# TDII_PWR_R00.net
KiCad netlist of a schematic drawn in Altium Designer
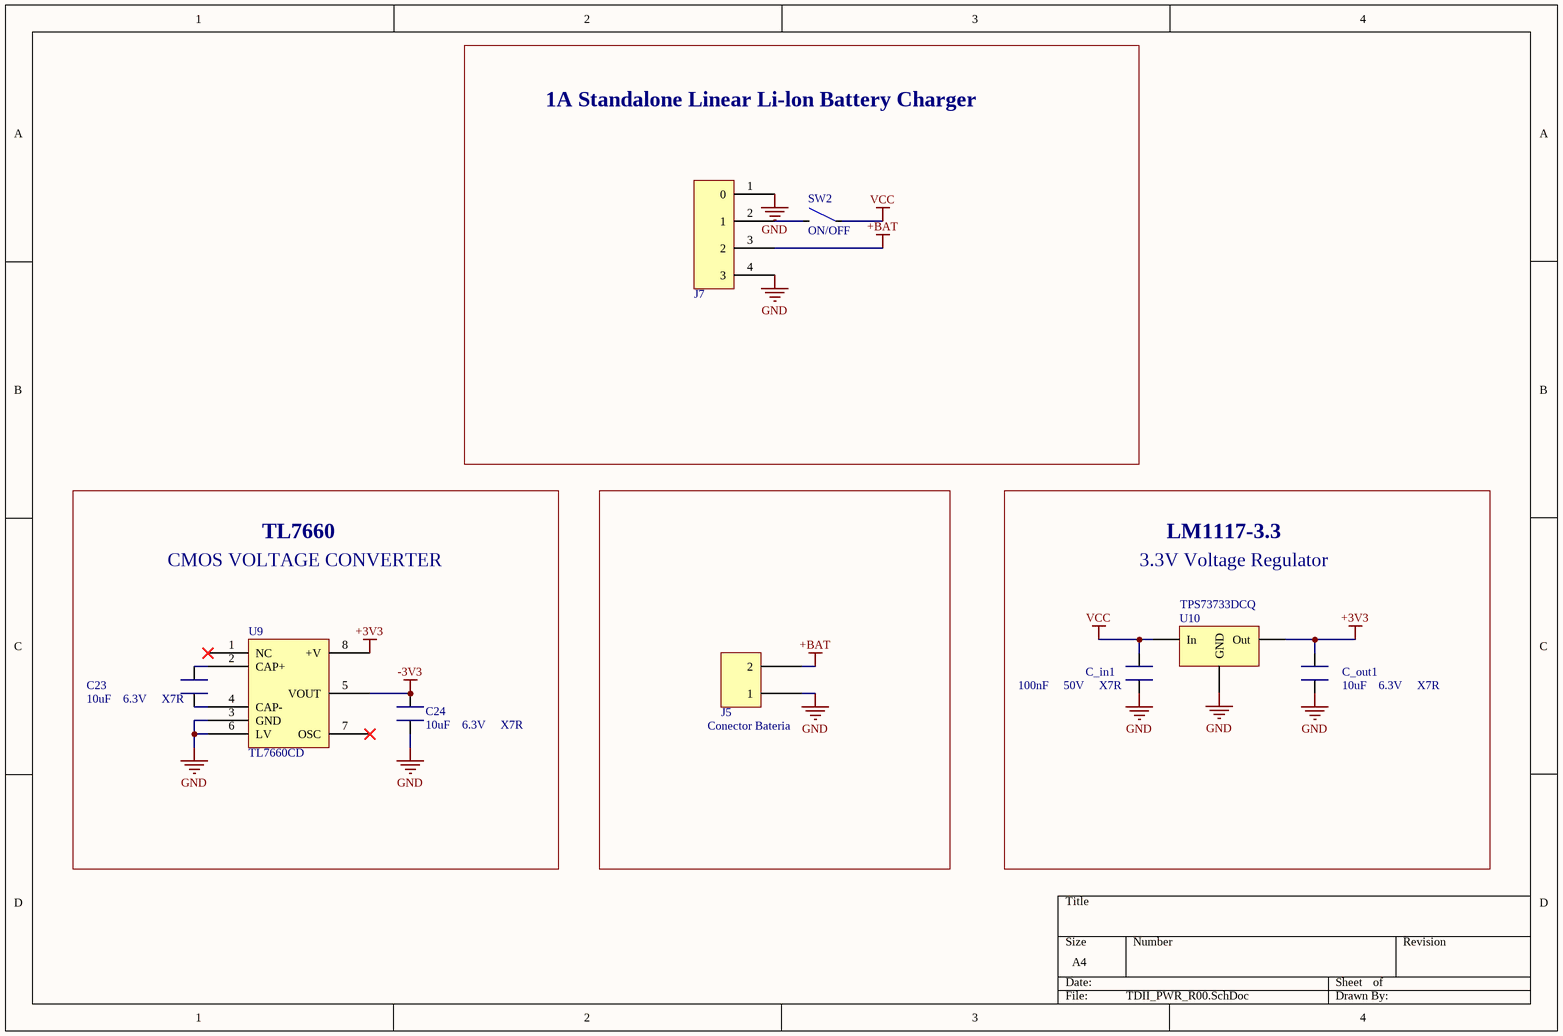
[diagram p0: TDII_PWR_R00.SchDoc]

(export (version "E")
  (design (tool "Eeschema 10.0.6"))
  (components
    (comp (ref "C23")
      (value "10uF    6.3V     X7R")
      (footprint "C_0805")
      (libsource (lib "TDII_SCH_LIB_R00") (part "CAP"))
    )
    (comp (ref "C24") (value "10uF    6.3V     X7R") (footprint "C_0805") (libsource (lib "") (part "CAP_1")))
    (comp (ref "C_in1")
      (value "100nF     50V     X7R")
      (footprint "C_0805")
      (libsource (lib "TDII_SCH_LIB_R00") (part "CAP"))
    )
    (comp (ref "C_out1")
      (value "10uF    6.3V     X7R")
      (footprint "C_0805")
      (libsource (lib "TDII_SCH_LIB_R00") (part "CAP"))
    )
    (comp (ref "J5")
      (value "Conector Bateria")
      (footprint "HEADER_1x2")
      (libsource (lib "TDII_SCH_LIB_R00") (part "Conector_2 ( 0.100{dblquote})"))
    )
    (comp (ref "J7")
      (value "Conector 0.100\" - 4 pines")
      (footprint "HEADER_CHARGER")
      (libsource (lib "Conectores") (part "Conector 0.100{dblquote} - 4 pines"))
    )
    (comp (ref "SW2")
      (value "ON/OFF")
      (footprint "HEADER_1x2")
      (description "Switch, generic")
      (libsource (lib "IFS_Altium") (part "SWITCH"))
    )
    (comp (ref "U9")
      (value "TL7660CD")
      (footprint "SOI8")
      (libsource (lib "TDII_SCH_LIB_R00") (part "TL7660"))
    )
    (comp (ref "U10")
      (value "TPS73733DCQ")
      (footprint "SOT-223-4")
      (description "LDO Voltage Regulators Sgl Output LDO 800mA Fixed Int Crnt limit")
      (fields (field (name "MANUFACTURER") "Texas Instruments"))
      (libsource (lib "IFS_Altium") (part "TLV1117-33CKVURG3"))
    )
  )
  (nets
    (net (code "1") (name "+3V3") (class "Default")
      (node (ref "C_out1") (pin "1") (pinfunction "1_1") (pintype "passive"))
      (node (ref "U10") (pin "2") (pinfunction "Out_2") (pintype "passive"))
      (node (ref "U9") (pin "8") (pinfunction "+V_8") (pintype "passive"))
    )
    (net (code "2") (name "+BAT") (class "Default")
      (node (ref "J5") (pin "1") (pinfunction "2_1") (pintype "passive"))
      (node (ref "J7") (pin "3") (pinfunction "2_3") (pintype "passive"))
    )
    (net (code "3") (name "-3V3") (class "Default")
      (node (ref "C24") (pin "1") (pinfunction "1_1") (pintype "passive"))
      (node (ref "U9") (pin "5") (pinfunction "VOUT_5") (pintype "passive"))
    )
    (net (code "4") (name "GND") (class "Default")
      (node (ref "C24") (pin "2") (pinfunction "2_2") (pintype "passive"))
      (node (ref "C_in1") (pin "2") (pinfunction "2_2") (pintype "passive"))
      (node (ref "C_out1") (pin "2") (pinfunction "2_2") (pintype "passive"))
      (node (ref "J5") (pin "2") (pinfunction "1_2") (pintype "passive"))
      (node (ref "J7") (pin "1") (pinfunction "0_1") (pintype "passive"))
      (node (ref "J7") (pin "4") (pinfunction "3_4") (pintype "passive"))
      (node (ref "U10") (pin "1") (pinfunction "GND_1") (pintype "passive"))
      (node (ref "U9") (pin "3") (pinfunction "GND_3") (pintype "passive"))
      (node (ref "U9") (pin "6") (pinfunction "LV_6") (pintype "passive"))
    )
    (net (code "5") (name "Net-(J7-1)") (class "Default")
      (node (ref "J7") (pin "2") (pinfunction "1_2") (pintype "passive"))
      (node (ref "SW2") (pin "1") (pinfunction "1_1") (pintype "passive"))
    )
    (net (code "6") (name "Net-(U9-CAP+)") (class "Default")
      (node (ref "C23") (pin "1") (pinfunction "1_1") (pintype "passive"))
      (node (ref "U9") (pin "2") (pinfunction "CAP+_2") (pintype "passive"))
    )
    (net (code "7") (name "Net-(U9-CAP-)") (class "Default")
      (node (ref "C23") (pin "2") (pinfunction "2_2") (pintype "passive"))
      (node (ref "U9") (pin "4") (pinfunction "CAP-_4") (pintype "passive"))
    )
    (net (code "8") (name "VCC") (class "Default")
      (node (ref "C_in1") (pin "1") (pinfunction "1_1") (pintype "passive"))
      (node (ref "SW2") (pin "2") (pinfunction "2_2") (pintype "passive"))
      (node (ref "U10") (pin "3") (pinfunction "In_3") (pintype "passive"))
    )
    (net (code "9") (name "unconnected-(U9-NC-Pad1)") (class "Default")
      (node (ref "U9") (pin "1") (pinfunction "NC_1") (pintype "passive+no_connect"))
    )
    (net (code "10") (name "unconnected-(U9-OSC-Pad7)") (class "Default")
      (node (ref "U9") (pin "7") (pinfunction "OSC_7") (pintype "passive+no_connect"))
    )
  )
)
